# PowerSupply.net
KiCad netlist of a schematic drawn in Altium Designer
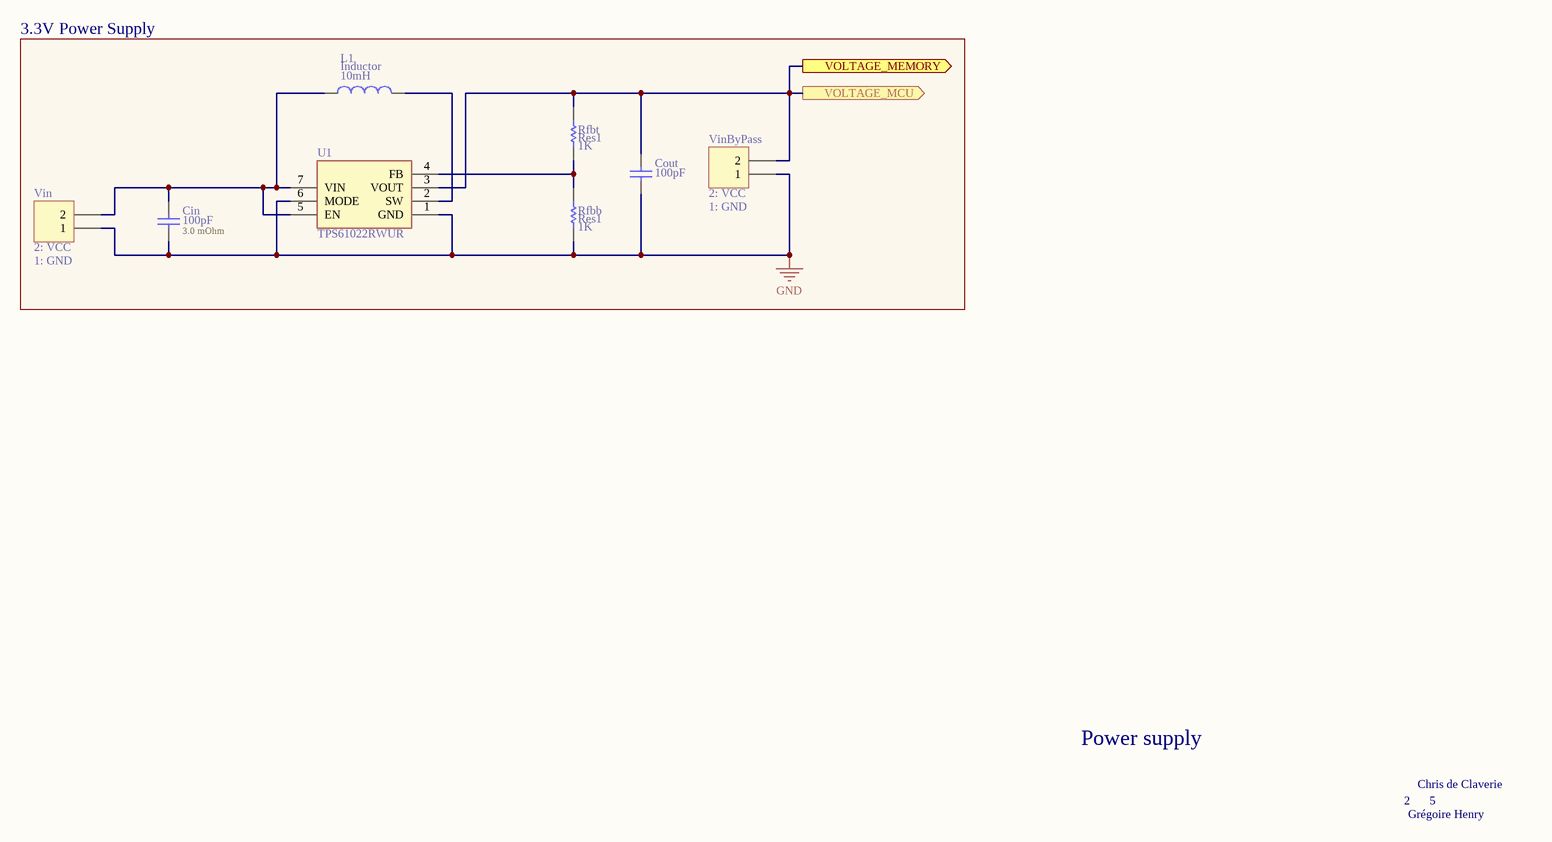
[diagram p0: PowerSupply.SchDoc]

(export (version "E")
  (design (tool "Eeschema 10.0.6"))
  (components
    (comp (ref "Cin")
      (value "100pF")
      (footprint "RAD-0.3")
      (description "Capacitor")
      (fields (field (name "Comment") "Cap") (field (name "PUBLISHER") "Altium Limited"))
      (libsource (lib "Miscellaneous Devices") (part "Cap"))
    )
    (comp (ref "Cout")
      (value "100pF")
      (footprint "RAD-0.3")
      (description "Capacitor")
      (fields (field (name "Comment") "Cap") (field (name "PUBLISHER") "Altium Limited"))
      (libsource (lib "Miscellaneous Devices") (part "Cap"))
    )
    (comp (ref "L1")
      (value "Inductor")
      (footprint "0402-A")
      (fields (field (name "ALTIUM_VALUE") "10mH") (field (name "PUBLISHER") "Altium Limited"))
      (libsource (lib "Miscellaneous Devices") (part "Inductor"))
    )
    (comp (ref "Rfbb")
      (value "Res1")
      (footprint "AXIAL-0.3")
      (description "Resistor")
      (fields (field (name "ALTIUM_VALUE") "1K") (field (name "PUBLISHER") "Altium Limited"))
      (libsource (lib "Miscellaneous Devices") (part "Res1"))
    )
    (comp (ref "Rfbt")
      (value "Res1")
      (footprint "AXIAL-0.3")
      (description "Resistor")
      (fields (field (name "ALTIUM_VALUE") "1K") (field (name "PUBLISHER") "Altium Limited"))
      (libsource (lib "Miscellaneous Devices") (part "Res1"))
    )
    (comp (ref "U1")
      (value "TPS61022RWUR")
      (footprint "SamacSys:TPS61022RWUR")
      (description "Power Supply")
      (fields (field (name "MOUSER PART NUMBER") "595-TPS61022RWUR"))
      (libsource (lib "SamacSys") (part "TPS61022RWUR"))
    )
    (comp (ref "Vin")
      (value "Header 2")
      (footprint "HDR1X2")
      (description "Header, 2-Pin")
      (fields (field (name "PUBLISHER") "Altium Limited"))
      (libsource (lib "Miscellaneous Connectors") (part "Header 2"))
    )
    (comp (ref "VinByPass")
      (value "Header 2")
      (footprint "HDR1X2")
      (description "Header, 2-Pin")
      (fields (field (name "PUBLISHER") "Altium Limited"))
      (libsource (lib "Miscellaneous Connectors") (part "Header 2"))
    )
  )
  (nets
    (net (code "1") (name "/VOLTAGE_MCU") (class "Default")
      (node (ref "Cout") (pin "2") (pinfunction "2_2") (pintype "passive"))
      (node (ref "Rfbt") (pin "2") (pinfunction "2_2") (pintype "passive"))
      (node (ref "U1") (pin "3") (pinfunction "VOUT_3") (pintype "passive"))
      (node (ref "VinByPass") (pin "2") (pinfunction "2_2") (pintype "passive"))
    )
    (net (code "2") (name "GND") (class "Default")
      (node (ref "Cin") (pin "1") (pinfunction "1_1") (pintype "passive"))
      (node (ref "Cout") (pin "1") (pinfunction "1_1") (pintype "passive"))
      (node (ref "Rfbb") (pin "1") (pinfunction "1_1") (pintype "passive"))
      (node (ref "U1") (pin "1") (pinfunction "GND_1") (pintype "passive"))
      (node (ref "U1") (pin "6") (pinfunction "MODE_6") (pintype "passive"))
      (node (ref "Vin") (pin "1") (pinfunction "1_1") (pintype "passive"))
      (node (ref "VinByPass") (pin "1") (pinfunction "1_1") (pintype "passive"))
    )
    (net (code "3") (name "Net-(U1-EN)") (class "Default")
      (node (ref "Cin") (pin "2") (pinfunction "2_2") (pintype "passive"))
      (node (ref "L1") (pin "1") (pinfunction "1_1") (pintype "passive"))
      (node (ref "U1") (pin "5") (pinfunction "EN_5") (pintype "passive"))
      (node (ref "U1") (pin "7") (pinfunction "VIN_7") (pintype "passive"))
      (node (ref "Vin") (pin "2") (pinfunction "2_2") (pintype "passive"))
    )
    (net (code "4") (name "Net-(U1-FB)") (class "Default")
      (node (ref "Rfbb") (pin "2") (pinfunction "2_2") (pintype "passive"))
      (node (ref "Rfbt") (pin "1") (pinfunction "1_1") (pintype "passive"))
      (node (ref "U1") (pin "4") (pinfunction "FB_4") (pintype "passive"))
    )
    (net (code "5") (name "Net-(U1-SW)") (class "Default")
      (node (ref "L1") (pin "2") (pinfunction "2_2") (pintype "passive"))
      (node (ref "U1") (pin "2") (pinfunction "SW_2") (pintype "passive"))
    )
  )
)
